# esp01-rs485.net
KiCad netlist of a schematic drawn in EAGLE
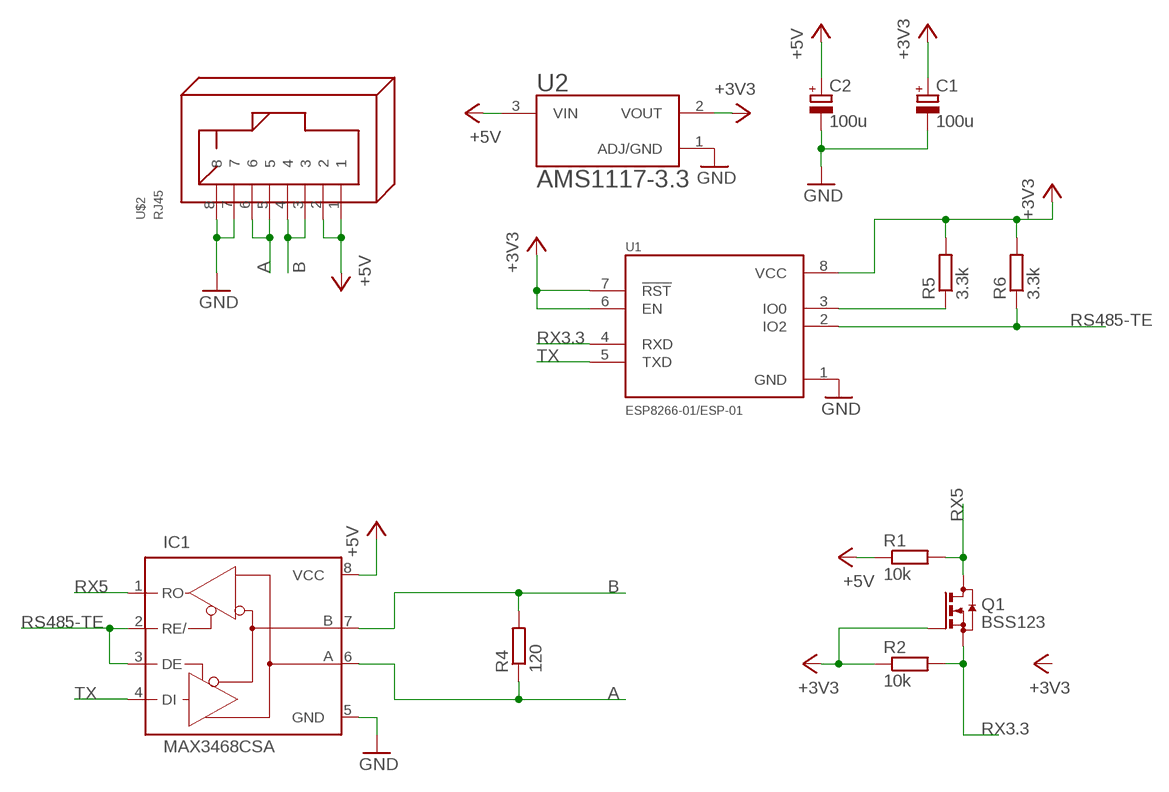
[diagram p0: schematic, sheet 1]

(export (version "E")
  (design (tool "Eeschema 10.0.6"))
  (components
    (comp (ref "C1")
      (value "100u")
      (footprint "eagle-import:E2,5-6")
      (libsource (lib "eagle-import") (part "CPOL-EUE2.5-6"))
    )
    (comp (ref "C2")
      (value "100u")
      (footprint "eagle-import:E2,5-6")
      (libsource (lib "eagle-import") (part "CPOL-EUE2.5-6"))
    )
    (comp (ref "IC1")
      (value "MAX3468CSA")
      (footprint "eagle-import:SO08")
      (fields (field (name "MPN") "MAX3468CSA+"))
      (libsource (lib "eagle-import") (part "MAX34SA68C"))
    )
    (comp (ref "Q1")
      (value "BSS123")
      (footprint "eagle-import:SOT23")
      (libsource (lib "eagle-import") (part "BSS123"))
    )
    (comp (ref "R1")
      (value "10k")
      (footprint "eagle-import:M1206")
      (libsource (lib "eagle-import") (part "R-EU_M1206"))
    )
    (comp (ref "R2")
      (value "10k")
      (footprint "eagle-import:M1206")
      (libsource (lib "eagle-import") (part "R-EU_M1206"))
    )
    (comp (ref "R4")
      (value "120")
      (footprint "eagle-import:M1206")
      (libsource (lib "eagle-import") (part "R-EU_M1206"))
    )
    (comp (ref "R5")
      (value "3.3k")
      (footprint "eagle-import:M1206")
      (libsource (lib "eagle-import") (part "R-EU_M1206"))
    )
    (comp (ref "R6")
      (value "3.3k")
      (footprint "eagle-import:M1206")
      (libsource (lib "eagle-import") (part "R-EU_M1206"))
    )
    (comp (ref "U$2")
      (value "RJ45")
      (footprint "eagle-import:RJ45")
      (libsource (lib "eagle-import") (part "RJ45"))
    )
    (comp (ref "U1")
      (value "ESP8266-01/ESP-01")
      (footprint "eagle-import:XCVR_ESP8266-01_ESP-01")
      (fields (field (name "MF") "AI-Thinker"))
      (libsource (lib "eagle-import") (part "ESP8266-01/ESP-01"))
    )
    (comp (ref "U2")
      (value "AMS1117-3.3")
      (footprint "eagle-import:SOT229P700X180-4N")
      (fields (field (name "MF") "Advanced Monolithic Systems"))
      (libsource (lib "eagle-import") (part "AMS1117-3.3"))
    )
  )
  (nets
    (net (code "1") (name "+3V3") (class "Default")
      (node (ref "C1") (pin "+") (pinfunction "+_+") (pintype "passive"))
      (node (ref "Q1") (pin "1") (pinfunction "G_1") (pintype "passive"))
      (node (ref "R2") (pin "1") (pinfunction "1_1") (pintype "passive"))
      (node (ref "R5") (pin "2") (pinfunction "2_2") (pintype "passive"))
      (node (ref "R6") (pin "2") (pinfunction "2_2") (pintype "passive"))
      (node (ref "U1") (pin "6") (pinfunction "EN_6") (pintype "input"))
      (node (ref "U1") (pin "7") (pinfunction "~{RST}_7") (pintype "input"))
      (node (ref "U1") (pin "8") (pinfunction "VCC_8") (pintype "power_in"))
      (node (ref "U2") (pin "2") (pinfunction "VOUT_2") (pintype "output"))
    )
    (net (code "2") (name "+5V") (class "Default")
      (node (ref "C2") (pin "+") (pinfunction "+_+") (pintype "passive"))
      (node (ref "IC1") (pin "8") (pinfunction "VCC_8") (pintype "power_in"))
      (node (ref "R1") (pin "1") (pinfunction "1_1") (pintype "passive"))
      (node (ref "U$2") (pin "1") (pinfunction "1_1") (pintype "bidirectional"))
      (node (ref "U$2") (pin "2") (pinfunction "2_2") (pintype "bidirectional"))
      (node (ref "U2") (pin "3") (pinfunction "VIN_3") (pintype "input"))
    )
    (net (code "3") (name "/A") (class "Default")
      (node (ref "IC1") (pin "6") (pinfunction "A_6") (pintype "passive"))
      (node (ref "R4") (pin "1") (pinfunction "1_1") (pintype "passive"))
      (node (ref "U$2") (pin "5") (pinfunction "5_5") (pintype "bidirectional"))
      (node (ref "U$2") (pin "6") (pinfunction "6_6") (pintype "bidirectional"))
    )
    (net (code "4") (name "/B") (class "Default")
      (node (ref "IC1") (pin "7") (pinfunction "B_7") (pintype "passive"))
      (node (ref "R4") (pin "2") (pinfunction "2_2") (pintype "passive"))
      (node (ref "U$2") (pin "3") (pinfunction "3_3") (pintype "bidirectional"))
      (node (ref "U$2") (pin "4") (pinfunction "4_4") (pintype "bidirectional"))
    )
    (net (code "5") (name "/RS485-TE") (class "Default")
      (node (ref "IC1") (pin "2") (pinfunction "RE/_2") (pintype "input"))
      (node (ref "IC1") (pin "3") (pinfunction "DE_3") (pintype "input"))
      (node (ref "R6") (pin "1") (pinfunction "1_1") (pintype "passive"))
      (node (ref "U1") (pin "2") (pinfunction "IO2_2") (pintype "bidirectional"))
    )
    (net (code "6") (name "/RX3.3") (class "Default")
      (node (ref "Q1") (pin "2") (pinfunction "S_2") (pintype "passive"))
      (node (ref "R2") (pin "2") (pinfunction "2_2") (pintype "passive"))
      (node (ref "U1") (pin "4") (pinfunction "RXD_4") (pintype "input"))
    )
    (net (code "7") (name "/RX5") (class "Default")
      (node (ref "IC1") (pin "1") (pinfunction "RO_1") (pintype "output"))
      (node (ref "Q1") (pin "3") (pinfunction "D_3") (pintype "passive"))
      (node (ref "R1") (pin "2") (pinfunction "2_2") (pintype "passive"))
    )
    (net (code "8") (name "/TX") (class "Default")
      (node (ref "IC1") (pin "4") (pinfunction "DI_4") (pintype "input"))
      (node (ref "U1") (pin "5") (pinfunction "TXD_5") (pintype "output"))
    )
    (net (code "9") (name "GND") (class "Default")
      (node (ref "C1") (pin "-") (pinfunction "-_-") (pintype "passive"))
      (node (ref "C2") (pin "-") (pinfunction "-_-") (pintype "passive"))
      (node (ref "IC1") (pin "5") (pinfunction "GND_5") (pintype "power_in"))
      (node (ref "U$2") (pin "7") (pinfunction "7_7") (pintype "bidirectional"))
      (node (ref "U$2") (pin "8") (pinfunction "8_8") (pintype "bidirectional"))
      (node (ref "U1") (pin "1") (pinfunction "GND_1") (pintype "power_in"))
      (node (ref "U2") (pin "1") (pinfunction "ADJ/GND_1") (pintype "power_in"))
    )
    (net (code "10") (name "Net-(U1-IO0)") (class "Default")
      (node (ref "R5") (pin "1") (pinfunction "1_1") (pintype "passive"))
      (node (ref "U1") (pin "3") (pinfunction "IO0_3") (pintype "bidirectional"))
    )
  )
)
